# SparkFun_Soil_Moisture_Sensor.net
KiCad netlist of a schematic drawn in EAGLE
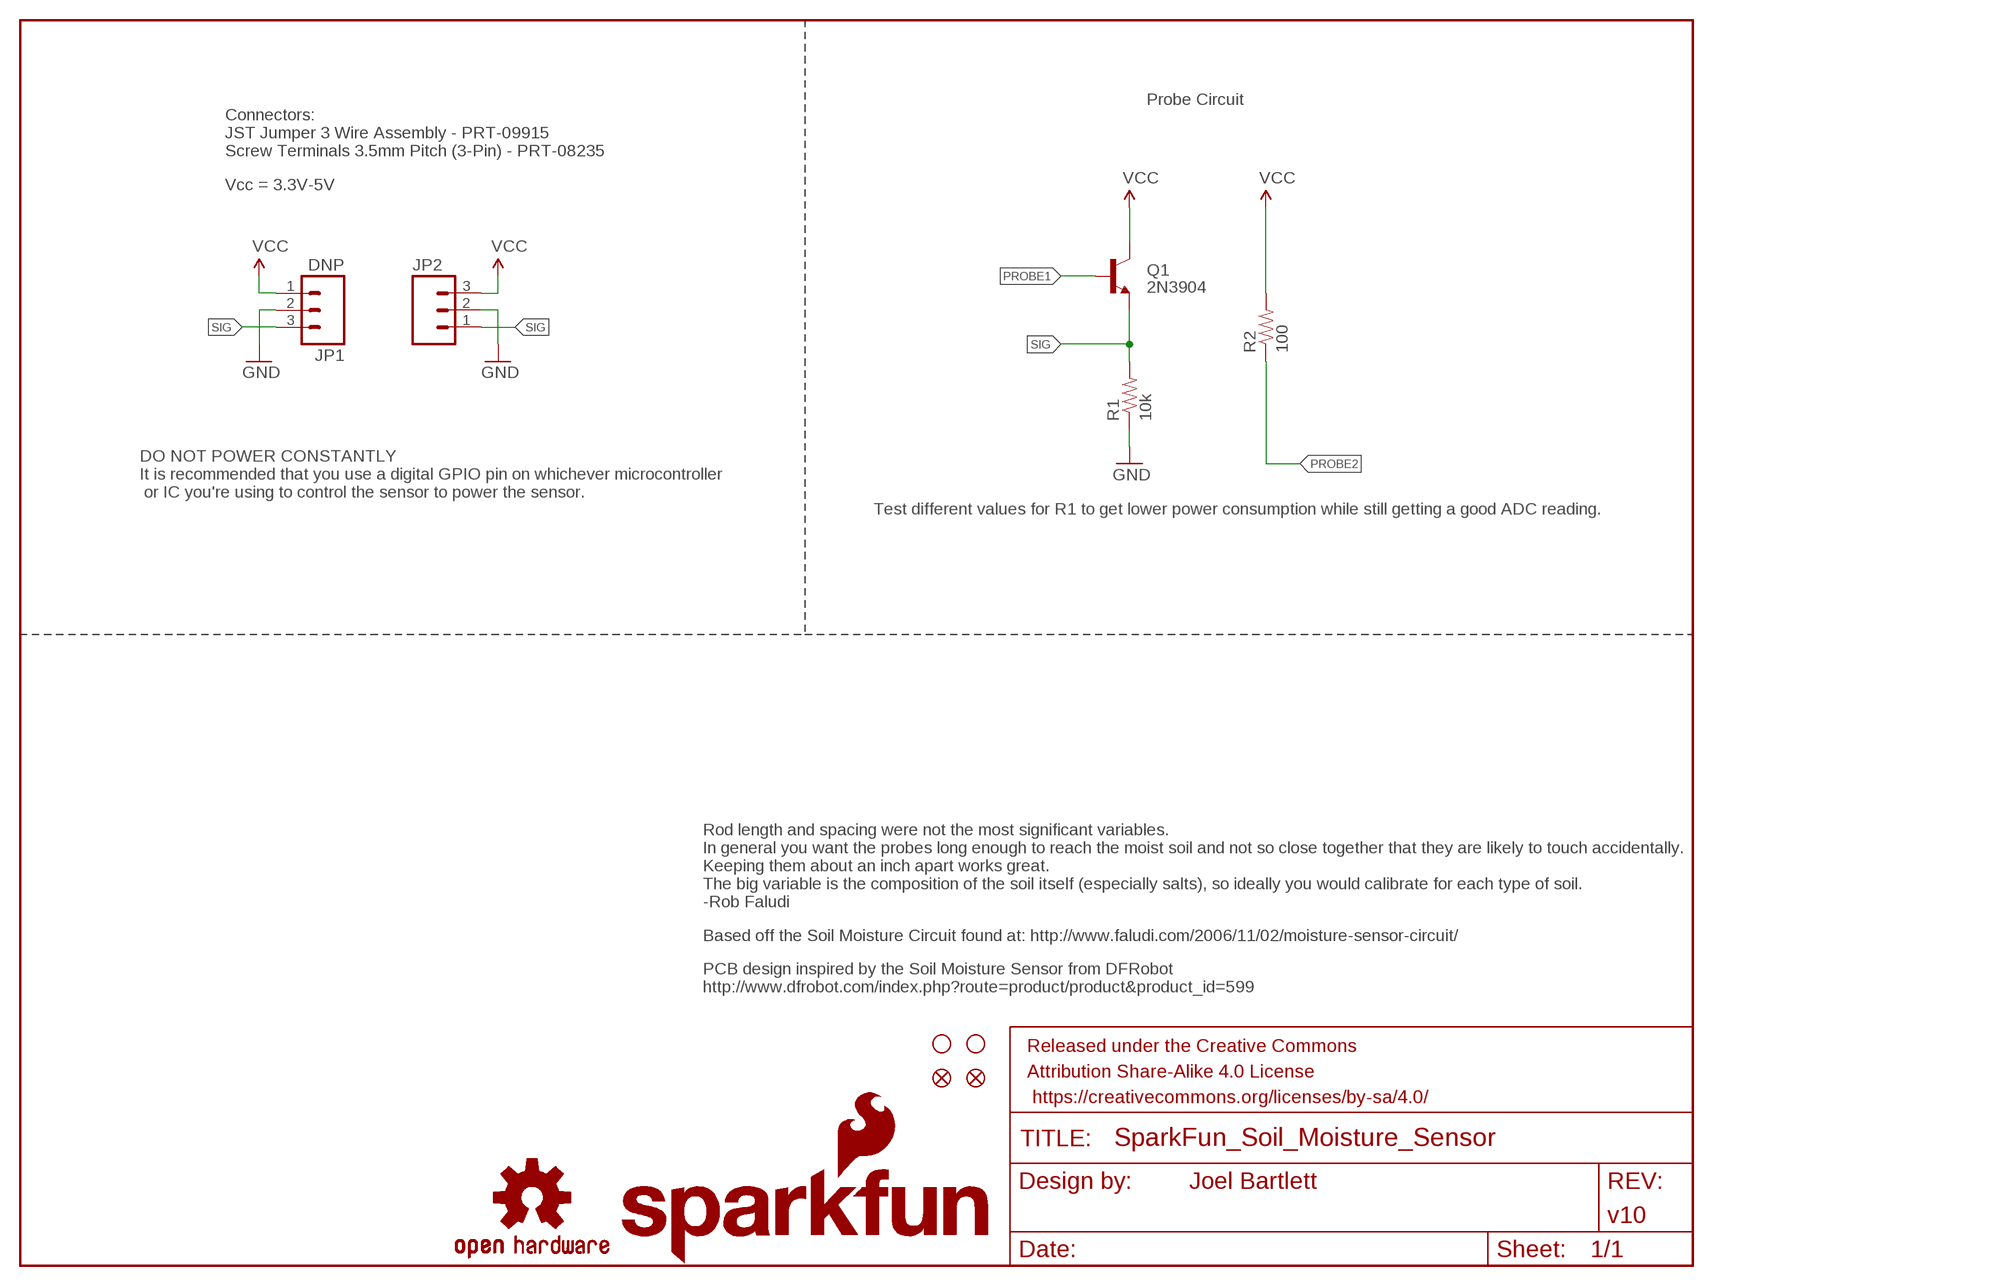
[diagram p0: schematic, sheet 1]

(export (version "E")
  (design (tool "Eeschema 10.0.6"))
  (components
    (comp (ref "FID1")
      (value "FIDUCIAL1X2")
      (footprint "eagle-import:FIDUCIAL-1X2")
      (libsource (lib "eagle-import") (part "FIDUCIAL1X2"))
    )
    (comp (ref "FID2")
      (value "FIDUCIAL1X2")
      (footprint "eagle-import:FIDUCIAL-1X2")
      (libsource (lib "eagle-import") (part "FIDUCIAL1X2"))
    )
    (comp (ref "FRAME1")
      (value "FRAME-LETTER")
      (footprint "eagle-import:CREATIVE_COMMONS")
      (fields
        (field (name "DESIGNER") "Joel Bartlett")
        (field (name "VERSION") "v10")
        (field (name "DESIGNER_1") "Joel Bartlett")
        (field (name "VERSION_1") "v10")
      )
      (libsource (lib "eagle-import") (part "FRAME-LETTER"))
    )
    (comp (ref "JP1")
      (value "DNP")
      (footprint "eagle-import:MOLEX-1X3")
      (libsource (lib "eagle-import") (part "M03POLAR"))
    )
    (comp (ref "JP2")
      (value "M03SCREW_LOCK")
      (footprint "eagle-import:SCREWTERMINAL-3.5MM-3_LOCK.007S")
      (libsource (lib "eagle-import") (part "M03SCREW_LOCK"))
    )
    (comp (ref "LOGO1")
      (value "SFE_LOGO_NAME_FLAME.1_INCH")
      (footprint "eagle-import:SFE_LOGO_NAME_FLAME_.1")
      (libsource (lib "eagle-import") (part "SFE_LOGO_NAME_FLAME.1_INCH"))
    )
    (comp (ref "LOGO2")
      (value "OSHW-LOGOS")
      (footprint "eagle-import:OSHW-LOGO-S")
      (libsource (lib "eagle-import") (part "OSHW-LOGOS"))
    )
    (comp (ref "Q1")
      (value "2N3904")
      (footprint "eagle-import:SOT23-3")
      (libsource (lib "eagle-import") (part "TRANSISTOR_NPNMMBT2222A"))
    )
    (comp (ref "R1")
      (value "10k")
      (footprint "eagle-import:0603-RES")
      (libsource (lib "eagle-import") (part "100OHM-1/4W-5%(0603)"))
    )
    (comp (ref "R2")
      (value "100")
      (footprint "eagle-import:0603-RES")
      (libsource (lib "eagle-import") (part "100OHM-1/4W-5%(0603)"))
    )
    (comp (ref "STANDOFF1")
      (value "STAND-OFF")
      (footprint "eagle-import:STAND-OFF")
      (libsource (lib "eagle-import") (part "STAND-OFF"))
    )
    (comp (ref "STANDOFF2")
      (value "STAND-OFF")
      (footprint "eagle-import:STAND-OFF")
      (libsource (lib "eagle-import") (part "STAND-OFF"))
    )
  )
  (nets
    (net (code "1") (name "GND") (class "Default")
      (node (ref "JP1") (pin "2") (pinfunction "2_2") (pintype "passive"))
      (node (ref "JP2") (pin "2") (pinfunction "2_2") (pintype "passive"))
      (node (ref "R1") (pin "1") (pinfunction "1_1") (pintype "passive"))
    )
    (net (code "2") (name "PROBE1") (class "Default")
      (node (ref "Q1") (pin "1") (pinfunction "B_1") (pintype "passive"))
    )
    (net (code "3") (name "PROBE2") (class "Default")
      (node (ref "R2") (pin "1") (pinfunction "1_1") (pintype "passive"))
    )
    (net (code "4") (name "SIG") (class "Default")
      (node (ref "JP1") (pin "3") (pinfunction "3_3") (pintype "passive"))
      (node (ref "JP2") (pin "1") (pinfunction "1_1") (pintype "passive"))
      (node (ref "Q1") (pin "2") (pinfunction "E_2") (pintype "passive"))
      (node (ref "R1") (pin "2") (pinfunction "2_2") (pintype "passive"))
    )
    (net (code "5") (name "VCC") (class "Default")
      (node (ref "JP1") (pin "1") (pinfunction "1_1") (pintype "passive"))
      (node (ref "JP2") (pin "3") (pinfunction "3_3") (pintype "passive"))
      (node (ref "Q1") (pin "3") (pinfunction "C_3") (pintype "passive"))
      (node (ref "R2") (pin "2") (pinfunction "2_2") (pintype "passive"))
    )
  )
)
